# PIC.net
KiCad netlist of a schematic drawn in Altium Designer
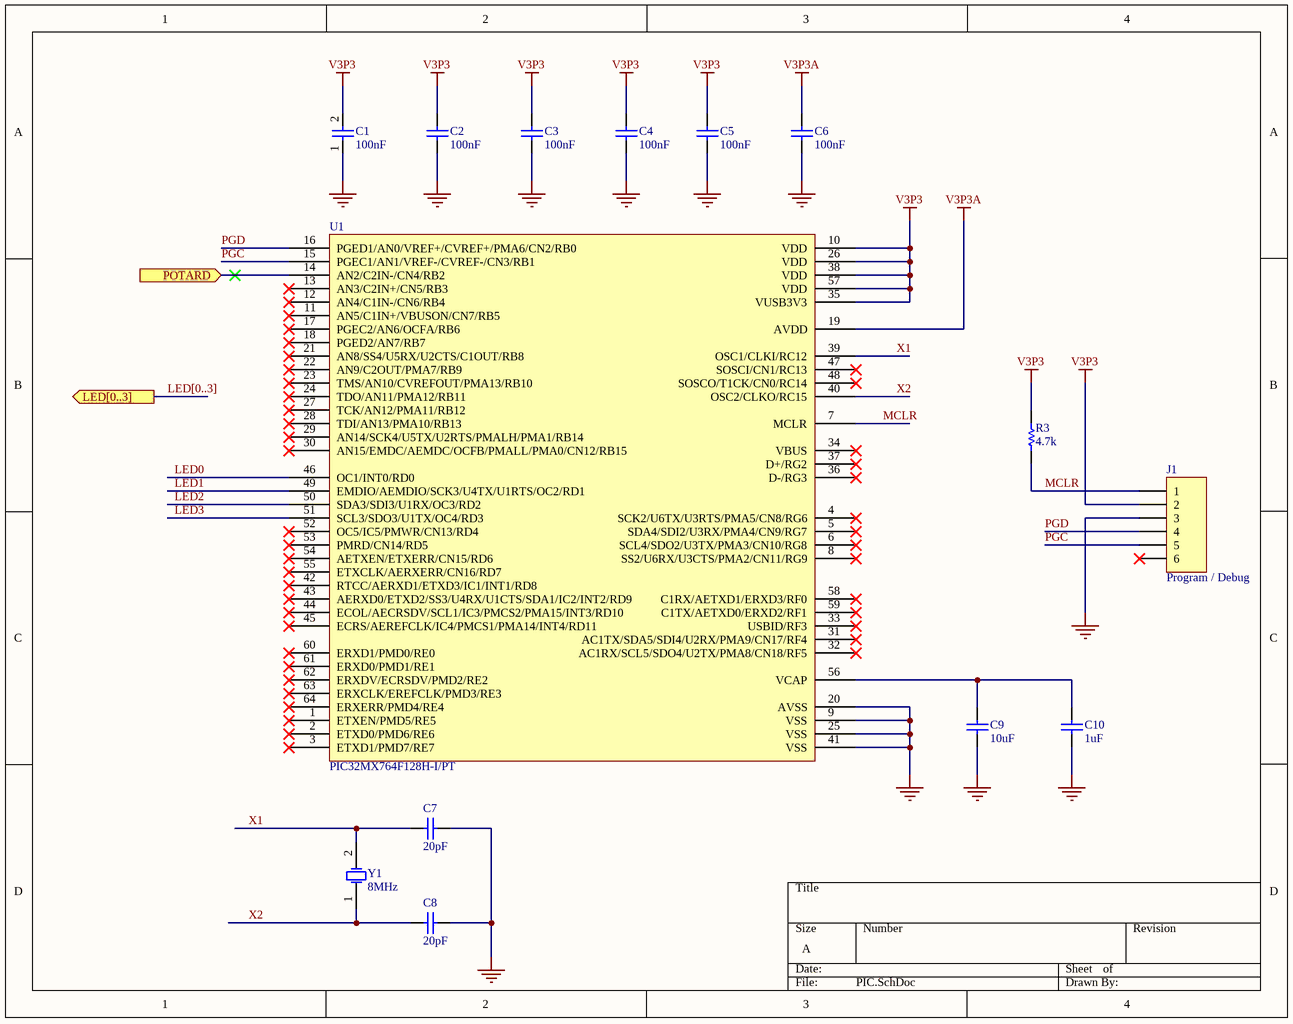
[diagram p0: PIC.SchDoc]

(export (version "E")
  (design (tool "Eeschema 10.0.6"))
  (components
    (comp (ref "C1")
      (value "100nF")
      (footprint "CAPC1608N")
      (description "Capacitor")
      (fields (field (name "PUBLISHER") "Altium Limited"))
      (libsource (lib "") (part "Cap_1"))
    )
    (comp (ref "C2")
      (value "100nF")
      (footprint "CAPC1608N")
      (description "Capacitor")
      (fields (field (name "PUBLISHER") "Altium Limited"))
      (libsource (lib "Miscellaneous Devices") (part "Cap"))
    )
    (comp (ref "C3")
      (value "100nF")
      (footprint "CAPC1608N")
      (description "Capacitor")
      (fields (field (name "PUBLISHER") "Altium Limited"))
      (libsource (lib "Miscellaneous Devices") (part "Cap"))
    )
    (comp (ref "C4")
      (value "100nF")
      (footprint "CAPC1608N")
      (description "Capacitor")
      (fields (field (name "PUBLISHER") "Altium Limited"))
      (libsource (lib "Miscellaneous Devices") (part "Cap"))
    )
    (comp (ref "C5")
      (value "100nF")
      (footprint "CAPC1608N")
      (description "Capacitor")
      (fields (field (name "PUBLISHER") "Altium Limited"))
      (libsource (lib "Miscellaneous Devices") (part "Cap"))
    )
    (comp (ref "C6")
      (value "100nF")
      (footprint "CAPC1608N")
      (description "Capacitor")
      (fields (field (name "PUBLISHER") "Altium Limited"))
      (libsource (lib "Miscellaneous Devices") (part "Cap"))
    )
    (comp (ref "C7")
      (value "20pF")
      (footprint "CAPC1005N")
      (description "Capacitor")
      (fields (field (name "PUBLISHER") "Altium Limited"))
      (libsource (lib "Miscellaneous Devices") (part "Cap"))
    )
    (comp (ref "C8")
      (value "20pF")
      (footprint "CAPC1005N")
      (description "Capacitor")
      (fields (field (name "PUBLISHER") "Altium Limited"))
      (libsource (lib "Miscellaneous Devices") (part "Cap"))
    )
    (comp (ref "C9")
      (value "10uF")
      (footprint "CAPC2012N")
      (description "Capacitor")
      (fields (field (name "PUBLISHER") "Altium Limited"))
      (libsource (lib "Miscellaneous Devices") (part "Cap"))
    )
    (comp (ref "C10")
      (value "1uF")
      (footprint "CAPC1608N")
      (description "Capacitor")
      (fields (field (name "PUBLISHER") "Altium Limited"))
      (libsource (lib "Miscellaneous Devices") (part "Cap"))
    )
    (comp (ref "J1")
      (value "Program / Debug")
      (footprint "RJ12_90  1-215876-3")
      (description "Header, 6-Pin")
      (fields (field (name "PUBLISHER") "Altium Limited"))
      (libsource (lib "Miscellaneous Connectors") (part "Header 6"))
    )
    (comp (ref "R3")
      (value "4.7k")
      (footprint "RESC1608N")
      (description "Resistor")
      (fields (field (name "PUBLISHER") "Altium Limited"))
      (libsource (lib "Miscellaneous Devices") (part "Res1"))
    )
    (comp (ref "U1")
      (value "PIC32MX764F128H-I/PT")
      (footprint "QFP50P1200X1200X120-64")
      (description "PIC32MX764F128H")
      (libsource (lib "PIC") (part "PIC32MX764F128H-I/PT"))
    )
    (comp (ref "Y1")
      (value "8MHz")
      (footprint "HC49/4H SMX CRYSTAL")
      (description "Crystal Oscillator")
      (fields (field (name "PUBLISHER") "Altium Limited"))
      (libsource (lib "Miscellaneous Devices") (part "XTAL"))
    )
  )
  (nets
    (net (code "1") (name "/LED0") (class "Default")
      (node (ref "U1") (pin "46") (pinfunction "OC1/INT0/RD0_46") (pintype "passive"))
    )
    (net (code "2") (name "/LED1") (class "Default")
      (node (ref "U1") (pin "49") (pinfunction "EMDIO/AEMDIO/SCK3/U4TX/U1RTS/OC2/RD1_49") (pintype "passive"))
    )
    (net (code "3") (name "/LED2") (class "Default")
      (node (ref "U1") (pin "50") (pinfunction "SDA3/SDI3/U1RX/OC3/RD2_50") (pintype "passive"))
    )
    (net (code "4") (name "/LED3") (class "Default")
      (node (ref "U1") (pin "51") (pinfunction "SCL3/SDO3/U1TX/OC4/RD3_51") (pintype "passive"))
    )
    (net (code "6") (name "/MCLR") (class "Default")
      (node (ref "J1") (pin "1") (pinfunction "1_1") (pintype "passive"))
      (node (ref "R3") (pin "1") (pinfunction "1_1") (pintype "passive"))
      (node (ref "U1") (pin "7") (pinfunction "MCLR_7") (pintype "passive"))
    )
    (net (code "7") (name "/PGC") (class "Default")
      (node (ref "J1") (pin "5") (pinfunction "5_5") (pintype "passive"))
      (node (ref "U1") (pin "15") (pinfunction "PGEC1/AN1/VREF-/CVREF-/CN3/RB1_15") (pintype "passive"))
    )
    (net (code "8") (name "/PGD") (class "Default")
      (node (ref "J1") (pin "4") (pinfunction "4_4") (pintype "passive"))
      (node (ref "U1") (pin "16") (pinfunction "PGED1/AN0/VREF+/CVREF+/PMA6/CN2/RB0_16") (pintype "passive"))
    )
    (net (code "9") (name "/POTARD") (class "Default")
      (node (ref "U1") (pin "14") (pinfunction "AN2/C2IN-/CN4/RB2_14") (pintype "passive+no_connect"))
    )
    (net (code "10") (name "/X1") (class "Default")
      (node (ref "C7") (pin "1") (pinfunction "1_1") (pintype "passive"))
      (node (ref "U1") (pin "39") (pinfunction "OSC1/CLKI/RC12_39") (pintype "passive"))
      (node (ref "Y1") (pin "2") (pinfunction "OSC2_2") (pintype "passive"))
    )
    (net (code "11") (name "/X2") (class "Default")
      (node (ref "C8") (pin "1") (pinfunction "1_1") (pintype "passive"))
      (node (ref "U1") (pin "40") (pinfunction "OSC2/CLKO/RC15_40") (pintype "passive"))
      (node (ref "Y1") (pin "1") (pinfunction "OSC1_1") (pintype "passive"))
    )
    (net (code "12") (name "GND") (class "Default")
      (node (ref "C1") (pin "1") (pinfunction "1_1") (pintype "passive"))
      (node (ref "C10") (pin "1") (pinfunction "1_1") (pintype "passive"))
      (node (ref "C2") (pin "1") (pinfunction "1_1") (pintype "passive"))
      (node (ref "C3") (pin "1") (pinfunction "1_1") (pintype "passive"))
      (node (ref "C4") (pin "1") (pinfunction "1_1") (pintype "passive"))
      (node (ref "C5") (pin "1") (pinfunction "1_1") (pintype "passive"))
      (node (ref "C6") (pin "1") (pinfunction "1_1") (pintype "passive"))
      (node (ref "C7") (pin "2") (pinfunction "2_2") (pintype "passive"))
      (node (ref "C8") (pin "2") (pinfunction "2_2") (pintype "passive"))
      (node (ref "C9") (pin "1") (pinfunction "1_1") (pintype "passive"))
      (node (ref "J1") (pin "3") (pinfunction "3_3") (pintype "passive"))
      (node (ref "U1") (pin "20") (pinfunction "AVSS_20") (pintype "passive"))
      (node (ref "U1") (pin "25") (pinfunction "VSS_25") (pintype "passive"))
      (node (ref "U1") (pin "41") (pinfunction "VSS_41") (pintype "passive"))
      (node (ref "U1") (pin "9") (pinfunction "VSS_9") (pintype "passive"))
    )
    (net (code "13") (name "Net-(U1-VCAP)") (class "Default")
      (node (ref "C10") (pin "2") (pinfunction "2_2") (pintype "passive"))
      (node (ref "C9") (pin "2") (pinfunction "2_2") (pintype "passive"))
      (node (ref "U1") (pin "56") (pinfunction "VCAP_56") (pintype "passive"))
    )
    (net (code "14") (name "V3P3") (class "Default")
      (node (ref "C1") (pin "2") (pinfunction "2_2") (pintype "passive"))
      (node (ref "C2") (pin "2") (pinfunction "2_2") (pintype "passive"))
      (node (ref "C3") (pin "2") (pinfunction "2_2") (pintype "passive"))
      (node (ref "C4") (pin "2") (pinfunction "2_2") (pintype "passive"))
      (node (ref "C5") (pin "2") (pinfunction "2_2") (pintype "passive"))
      (node (ref "J1") (pin "2") (pinfunction "2_2") (pintype "passive"))
      (node (ref "R3") (pin "2") (pinfunction "2_2") (pintype "passive"))
      (node (ref "U1") (pin "10") (pinfunction "VDD_10") (pintype "passive"))
      (node (ref "U1") (pin "26") (pinfunction "VDD_26") (pintype "passive"))
      (node (ref "U1") (pin "35") (pinfunction "VUSB3V3_35") (pintype "passive"))
      (node (ref "U1") (pin "38") (pinfunction "VDD_38") (pintype "passive"))
      (node (ref "U1") (pin "57") (pinfunction "VDD_57") (pintype "passive"))
    )
    (net (code "15") (name "V3P3A") (class "Default")
      (node (ref "C6") (pin "2") (pinfunction "2_2") (pintype "passive"))
      (node (ref "U1") (pin "19") (pinfunction "AVDD_19") (pintype "passive"))
    )
    (net (code "16") (name "unconnected-(J1-Pad6)") (class "Default")
      (node (ref "J1") (pin "6") (pinfunction "6_6") (pintype "passive+no_connect"))
    )
    (net (code "17") (name "unconnected-(U1-AC1RX{slash}SCL5{slash}SDO4{slash}U2TX{slash}PMA8{slash}CN18{slash}RF5-Pad32)") (class "Default")
      (node (ref "U1") (pin "32") (pinfunction "AC1RX/SCL5/SDO4/U2TX/PMA8/CN18/RF5_32") (pintype "passive+no_connect"))
    )
    (net (code "18") (name "unconnected-(U1-AC1TX{slash}SDA5{slash}SDI4{slash}U2RX{slash}PMA9{slash}CN17{slash}RF4-Pad31)") (class "Default")
      (node (ref "U1") (pin "31") (pinfunction "AC1TX/SDA5/SDI4/U2RX/PMA9/CN17/RF4_31") (pintype "passive+no_connect"))
    )
    (net (code "19") (name "unconnected-(U1-AERXD0{slash}ETXD2{slash}SS3{slash}U4RX{slash}U1CTS{slash}SDA1{slash}IC2{slash}INT2{slash}RD9-Pad43)") (class "Default")
      (node (ref "U1") (pin "43") (pinfunction "AERXD0/ETXD2/SS3/U4RX/U1CTS/SDA1/IC2/INT2/RD9_43") (pintype "passive+no_connect"))
    )
    (net (code "20") (name "unconnected-(U1-AETXEN{slash}ETXERR{slash}CN15{slash}RD6-Pad54)") (class "Default")
      (node (ref "U1") (pin "54") (pinfunction "AETXEN/ETXERR/CN15/RD6_54") (pintype "passive+no_connect"))
    )
    (net (code "21") (name "unconnected-(U1-AN3{slash}C2IN+{slash}CN5{slash}RB3-Pad13)") (class "Default")
      (node (ref "U1") (pin "13") (pinfunction "AN3/C2IN+/CN5/RB3_13") (pintype "passive+no_connect"))
    )
    (net (code "22") (name "unconnected-(U1-AN4{slash}C1IN-{slash}CN6{slash}RB4-Pad12)") (class "Default")
      (node (ref "U1") (pin "12") (pinfunction "AN4/C1IN-/CN6/RB4_12") (pintype "passive+no_connect"))
    )
    (net (code "23") (name "unconnected-(U1-AN5{slash}C1IN+{slash}VBUSON{slash}CN7{slash}RB5-Pad11)") (class "Default")
      (node (ref "U1") (pin "11") (pinfunction "AN5/C1IN+/VBUSON/CN7/RB5_11") (pintype "passive+no_connect"))
    )
    (net (code "24") (name "unconnected-(U1-AN8{slash}SS4{slash}U5RX{slash}U2CTS{slash}C1OUT{slash}RB8-Pad21)") (class "Default")
      (node (ref "U1") (pin "21") (pinfunction "AN8/SS4/U5RX/U2CTS/C1OUT/RB8_21") (pintype "passive+no_connect"))
    )
    (net (code "25") (name "unconnected-(U1-AN9{slash}C2OUT{slash}PMA7{slash}RB9-Pad22)") (class "Default")
      (node (ref "U1") (pin "22") (pinfunction "AN9/C2OUT/PMA7/RB9_22") (pintype "passive+no_connect"))
    )
    (net (code "26") (name "unconnected-(U1-AN14{slash}SCK4{slash}U5TX{slash}U2RTS{slash}PMALH{slash}PMA1{slash}RB14-Pad29)") (class "Default")
      (node (ref "U1") (pin "29") (pinfunction "AN14/SCK4/U5TX/U2RTS/PMALH/PMA1/RB14_29") (pintype "passive+no_connect"))
    )
    (net (code "27") (name "unconnected-(U1-AN15{slash}EMDC{slash}AEMDC{slash}OCFB{slash}PMALL{slash}PMA0{slash}CN12{slash}RB15-Pad30)") (class "Default")
      (node (ref "U1") (pin "30") (pinfunction "AN15/EMDC/AEMDC/OCFB/PMALL/PMA0/CN12/RB15_30") (pintype "passive+no_connect"))
    )
    (net (code "28") (name "unconnected-(U1-C1RX{slash}AETXD1{slash}ERXD3{slash}RF0-Pad58)") (class "Default")
      (node (ref "U1") (pin "58") (pinfunction "C1RX/AETXD1/ERXD3/RF0_58") (pintype "passive+no_connect"))
    )
    (net (code "29") (name "unconnected-(U1-C1TX{slash}AETXD0{slash}ERXD2{slash}RF1-Pad59)") (class "Default")
      (node (ref "U1") (pin "59") (pinfunction "C1TX/AETXD0/ERXD2/RF1_59") (pintype "passive+no_connect"))
    )
    (net (code "30") (name "unconnected-(U1-D+{slash}RG2-Pad37)") (class "Default")
      (node (ref "U1") (pin "37") (pinfunction "D+/RG2_37") (pintype "passive+no_connect"))
    )
    (net (code "31") (name "unconnected-(U1-D-{slash}RG3-Pad36)") (class "Default")
      (node (ref "U1") (pin "36") (pinfunction "D-/RG3_36") (pintype "passive+no_connect"))
    )
    (net (code "32") (name "unconnected-(U1-ECOL{slash}AECRSDV{slash}SCL1{slash}IC3{slash}PMCS2{slash}PMA15{slash}INT3{slash}RD10-Pad44)") (class "Default")
      (node (ref "U1") (pin "44") (pinfunction "ECOL/AECRSDV/SCL1/IC3/PMCS2/PMA15/INT3/RD10_44") (pintype "passive+no_connect"))
    )
    (net (code "33") (name "unconnected-(U1-ECRS{slash}AEREFCLK{slash}IC4{slash}PMCS1{slash}PMA14{slash}INT4{slash}RD11-Pad45)") (class "Default")
      (node (ref "U1") (pin "45") (pinfunction "ECRS/AEREFCLK/IC4/PMCS1/PMA14/INT4/RD11_45") (pintype "passive+no_connect"))
    )
    (net (code "34") (name "unconnected-(U1-ERXCLK{slash}EREFCLK{slash}PMD3{slash}RE3-Pad63)") (class "Default")
      (node (ref "U1") (pin "63") (pinfunction "ERXCLK/EREFCLK/PMD3/RE3_63") (pintype "passive+no_connect"))
    )
    (net (code "35") (name "unconnected-(U1-ERXD0{slash}PMD1{slash}RE1-Pad61)") (class "Default")
      (node (ref "U1") (pin "61") (pinfunction "ERXD0/PMD1/RE1_61") (pintype "passive+no_connect"))
    )
    (net (code "36") (name "unconnected-(U1-ERXD1{slash}PMD0{slash}RE0-Pad60)") (class "Default")
      (node (ref "U1") (pin "60") (pinfunction "ERXD1/PMD0/RE0_60") (pintype "passive+no_connect"))
    )
    (net (code "37") (name "unconnected-(U1-ERXDV{slash}ECRSDV{slash}PMD2{slash}RE2-Pad62)") (class "Default")
      (node (ref "U1") (pin "62") (pinfunction "ERXDV/ECRSDV/PMD2/RE2_62") (pintype "passive+no_connect"))
    )
    (net (code "38") (name "unconnected-(U1-ERXERR{slash}PMD4{slash}RE4-Pad64)") (class "Default")
      (node (ref "U1") (pin "64") (pinfunction "ERXERR/PMD4/RE4_64") (pintype "passive+no_connect"))
    )
    (net (code "39") (name "unconnected-(U1-ETXCLK{slash}AERXERR{slash}CN16{slash}RD7-Pad55)") (class "Default")
      (node (ref "U1") (pin "55") (pinfunction "ETXCLK/AERXERR/CN16/RD7_55") (pintype "passive+no_connect"))
    )
    (net (code "40") (name "unconnected-(U1-ETXD0{slash}PMD6{slash}RE6-Pad2)") (class "Default")
      (node (ref "U1") (pin "2") (pinfunction "ETXD0/PMD6/RE6_2") (pintype "passive+no_connect"))
    )
    (net (code "41") (name "unconnected-(U1-ETXD1{slash}PMD7{slash}RE7-Pad3)") (class "Default")
      (node (ref "U1") (pin "3") (pinfunction "ETXD1/PMD7/RE7_3") (pintype "passive+no_connect"))
    )
    (net (code "42") (name "unconnected-(U1-ETXEN{slash}PMD5{slash}RE5-Pad1)") (class "Default")
      (node (ref "U1") (pin "1") (pinfunction "ETXEN/PMD5/RE5_1") (pintype "passive+no_connect"))
    )
    (net (code "43") (name "unconnected-(U1-OC5{slash}IC5{slash}PMWR{slash}CN13{slash}RD4-Pad52)") (class "Default")
      (node (ref "U1") (pin "52") (pinfunction "OC5/IC5/PMWR/CN13/RD4_52") (pintype "passive+no_connect"))
    )
    (net (code "44") (name "unconnected-(U1-PGEC2{slash}AN6{slash}OCFA{slash}RB6-Pad17)") (class "Default")
      (node (ref "U1") (pin "17") (pinfunction "PGEC2/AN6/OCFA/RB6_17") (pintype "passive+no_connect"))
    )
    (net (code "45") (name "unconnected-(U1-PGED2{slash}AN7{slash}RB7-Pad18)") (class "Default")
      (node (ref "U1") (pin "18") (pinfunction "PGED2/AN7/RB7_18") (pintype "passive+no_connect"))
    )
    (net (code "46") (name "unconnected-(U1-PMRD{slash}CN14{slash}RD5-Pad53)") (class "Default")
      (node (ref "U1") (pin "53") (pinfunction "PMRD/CN14/RD5_53") (pintype "passive+no_connect"))
    )
    (net (code "47") (name "unconnected-(U1-RTCC{slash}AERXD1{slash}ETXD3{slash}IC1{slash}INT1{slash}RD8-Pad42)") (class "Default")
      (node (ref "U1") (pin "42") (pinfunction "RTCC/AERXD1/ETXD3/IC1/INT1/RD8_42") (pintype "passive+no_connect"))
    )
    (net (code "48") (name "unconnected-(U1-SCK2{slash}U6TX{slash}U3RTS{slash}PMA5{slash}CN8{slash}RG6-Pad4)") (class "Default")
      (node (ref "U1") (pin "4") (pinfunction "SCK2/U6TX/U3RTS/PMA5/CN8/RG6_4") (pintype "passive+no_connect"))
    )
    (net (code "49") (name "unconnected-(U1-SCL4{slash}SDO2{slash}U3TX{slash}PMA3{slash}CN10{slash}RG8-Pad6)") (class "Default")
      (node (ref "U1") (pin "6") (pinfunction "SCL4/SDO2/U3TX/PMA3/CN10/RG8_6") (pintype "passive+no_connect"))
    )
    (net (code "50") (name "unconnected-(U1-SDA4{slash}SDI2{slash}U3RX{slash}PMA4{slash}CN9{slash}RG7-Pad5)") (class "Default")
      (node (ref "U1") (pin "5") (pinfunction "SDA4/SDI2/U3RX/PMA4/CN9/RG7_5") (pintype "passive+no_connect"))
    )
    (net (code "51") (name "unconnected-(U1-SOSCI{slash}CN1{slash}RC13-Pad47)") (class "Default")
      (node (ref "U1") (pin "47") (pinfunction "SOSCI/CN1/RC13_47") (pintype "passive+no_connect"))
    )
    (net (code "52") (name "unconnected-(U1-SOSCO{slash}T1CK{slash}CN0{slash}RC14-Pad48)") (class "Default")
      (node (ref "U1") (pin "48") (pinfunction "SOSCO/T1CK/CN0/RC14_48") (pintype "passive+no_connect"))
    )
    (net (code "53") (name "unconnected-(U1-SS2{slash}U6RX{slash}U3CTS{slash}PMA2{slash}CN11{slash}RG9-Pad8)") (class "Default")
      (node (ref "U1") (pin "8") (pinfunction "SS2/U6RX/U3CTS/PMA2/CN11/RG9_8") (pintype "passive+no_connect"))
    )
    (net (code "54") (name "unconnected-(U1-TCK{slash}AN12{slash}PMA11{slash}RB12-Pad27)") (class "Default")
      (node (ref "U1") (pin "27") (pinfunction "TCK/AN12/PMA11/RB12_27") (pintype "passive+no_connect"))
    )
    (net (code "55") (name "unconnected-(U1-TDI{slash}AN13{slash}PMA10{slash}RB13-Pad28)") (class "Default")
      (node (ref "U1") (pin "28") (pinfunction "TDI/AN13/PMA10/RB13_28") (pintype "passive+no_connect"))
    )
    (net (code "56") (name "unconnected-(U1-TDO{slash}AN11{slash}PMA12{slash}RB11-Pad24)") (class "Default")
      (node (ref "U1") (pin "24") (pinfunction "TDO/AN11/PMA12/RB11_24") (pintype "passive+no_connect"))
    )
    (net (code "57") (name "unconnected-(U1-TMS{slash}AN10{slash}CVREFOUT{slash}PMA13{slash}RB10-Pad23)") (class "Default")
      (node (ref "U1") (pin "23") (pinfunction "TMS/AN10/CVREFOUT/PMA13/RB10_23") (pintype "passive+no_connect"))
    )
    (net (code "58") (name "unconnected-(U1-USBID{slash}RF3-Pad33)") (class "Default")
      (node (ref "U1") (pin "33") (pinfunction "USBID/RF3_33") (pintype "passive+no_connect"))
    )
    (net (code "59") (name "unconnected-(U1-VBUS-Pad34)") (class "Default")
      (node (ref "U1") (pin "34") (pinfunction "VBUS_34") (pintype "passive+no_connect"))
    )
  )
)
